# rfm12_breakout_board.net
KiCad netlist of a schematic drawn in EAGLE
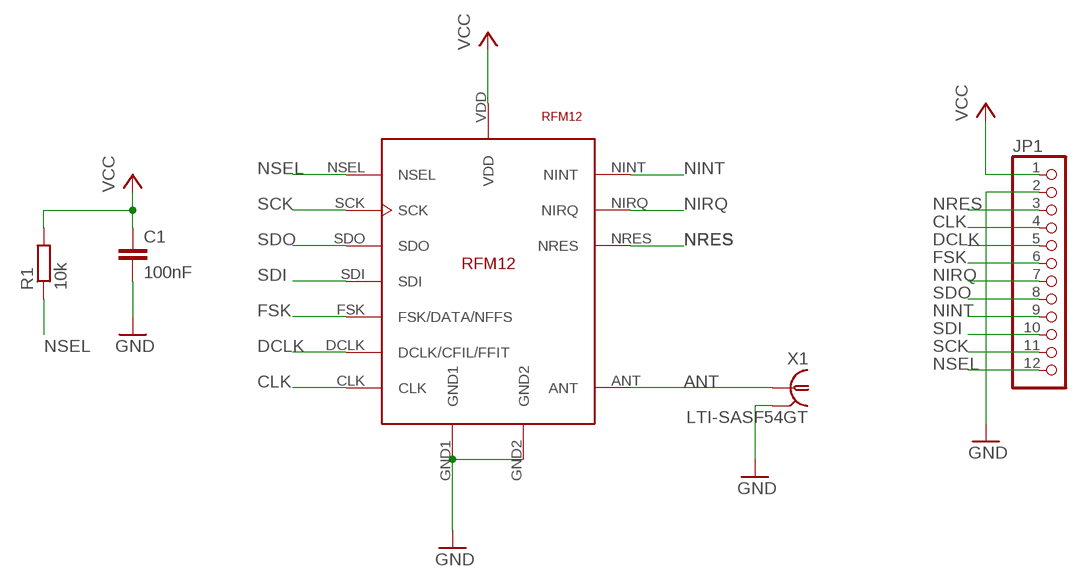
[diagram p0: schematic, sheet 1]

(export (version "E")
  (design (tool "Eeschema 10.0.6"))
  (components
    (comp (ref "C1")
      (value "100nF")
      (footprint "eagle-import:C0805")
      (libsource (lib "eagle-import") (part "C-EUC0805"))
    )
    (comp (ref "JP1")
      (value "PINHD-1X12/90")
      (footprint "eagle-import:1X12_90")
      (libsource (lib "eagle-import") (part "PINHD-1X12/90"))
    )
    (comp (ref "R1")
      (value "10k")
      (footprint "eagle-import:M0805")
      (libsource (lib "eagle-import") (part "R-EU_M0805"))
    )
    (comp (ref "U$1")
      (value "RFM12")
      (footprint "eagle-import:RFM12")
      (libsource (lib "eagle-import") (part "RFM12"))
    )
    (comp (ref "X1")
      (value "LTI-SASF54GT")
      (footprint "eagle-import:LTI-SASF54GT")
      (libsource (lib "eagle-import") (part "LTI-SASF54GT"))
    )
  )
  (nets
    (net (code "1") (name "/ANT") (class "Default")
      (node (ref "U$1") (pin "ANT") (pinfunction "ANT_ANT") (pintype "bidirectional"))
      (node (ref "X1") (pin "1") (pinfunction "1_1") (pintype "passive"))
    )
    (net (code "2") (name "/CLK") (class "Default")
      (node (ref "JP1") (pin "4") (pinfunction "4_4") (pintype "passive"))
      (node (ref "U$1") (pin "CLK") (pinfunction "CLK_CLK") (pintype "output"))
    )
    (net (code "3") (name "/DCLK") (class "Default")
      (node (ref "JP1") (pin "5") (pinfunction "5_5") (pintype "passive"))
      (node (ref "U$1") (pin "DCLK") (pinfunction "DCLK/CFIL/FFIT_DCLK") (pintype "bidirectional"))
    )
    (net (code "4") (name "/FSK") (class "Default")
      (node (ref "JP1") (pin "6") (pinfunction "6_6") (pintype "passive"))
      (node (ref "U$1") (pin "FSK") (pinfunction "FSK/DATA/NFFS_FSK") (pintype "bidirectional"))
    )
    (net (code "5") (name "/NINT") (class "Default")
      (node (ref "JP1") (pin "9") (pinfunction "9_9") (pintype "passive"))
      (node (ref "U$1") (pin "NINT") (pinfunction "NINT_NINT") (pintype "bidirectional"))
    )
    (net (code "6") (name "/NIRQ") (class "Default")
      (node (ref "JP1") (pin "7") (pinfunction "7_7") (pintype "passive"))
      (node (ref "U$1") (pin "NIRQ") (pinfunction "NIRQ_NIRQ") (pintype "output"))
    )
    (net (code "7") (name "/NRES") (class "Default")
      (node (ref "JP1") (pin "3") (pinfunction "3_3") (pintype "passive"))
      (node (ref "U$1") (pin "NRES") (pinfunction "NRES_NRES") (pintype "bidirectional"))
    )
    (net (code "8") (name "/NSEL") (class "Default")
      (node (ref "JP1") (pin "12") (pinfunction "12_12") (pintype "passive"))
      (node (ref "R1") (pin "1") (pinfunction "1_1") (pintype "passive"))
      (node (ref "U$1") (pin "NSEL") (pinfunction "NSEL_NSEL") (pintype "input"))
    )
    (net (code "9") (name "/SCK") (class "Default")
      (node (ref "JP1") (pin "11") (pinfunction "11_11") (pintype "passive"))
      (node (ref "U$1") (pin "SCK") (pinfunction "SCK_SCK") (pintype "input"))
    )
    (net (code "10") (name "/SDI") (class "Default")
      (node (ref "JP1") (pin "10") (pinfunction "10_10") (pintype "passive"))
      (node (ref "U$1") (pin "SDI") (pinfunction "SDI_SDI") (pintype "input"))
    )
    (net (code "11") (name "/SDO") (class "Default")
      (node (ref "JP1") (pin "8") (pinfunction "8_8") (pintype "passive"))
      (node (ref "U$1") (pin "SDO") (pinfunction "SDO_SDO") (pintype "output"))
    )
    (net (code "12") (name "GND") (class "Default")
      (node (ref "C1") (pin "2") (pinfunction "2_2") (pintype "passive"))
      (node (ref "JP1") (pin "2") (pinfunction "2_2") (pintype "passive"))
      (node (ref "U$1") (pin "GND1") (pinfunction "GND1_GND1") (pintype "passive"))
      (node (ref "U$1") (pin "GND2") (pinfunction "GND2_GND2") (pintype "passive"))
      (node (ref "X1") (pin "2") (pinfunction "2_2") (pintype "passive"))
      (node (ref "X1") (pin "3") (pinfunction "2_3") (pintype "passive"))
      (node (ref "X1") (pin "4") (pinfunction "2_4") (pintype "passive"))
      (node (ref "X1") (pin "5") (pinfunction "2_5") (pintype "passive"))
    )
    (net (code "13") (name "VCC") (class "Default")
      (node (ref "C1") (pin "1") (pinfunction "1_1") (pintype "passive"))
      (node (ref "JP1") (pin "1") (pinfunction "1_1") (pintype "passive"))
      (node (ref "R1") (pin "2") (pinfunction "2_2") (pintype "passive"))
      (node (ref "U$1") (pin "VDD") (pinfunction "VDD_VDD") (pintype "power_in"))
    )
  )
)
